# J-Link-OB-STM32F103C8T6.net
KiCad netlist of a schematic drawn in Altium Designer
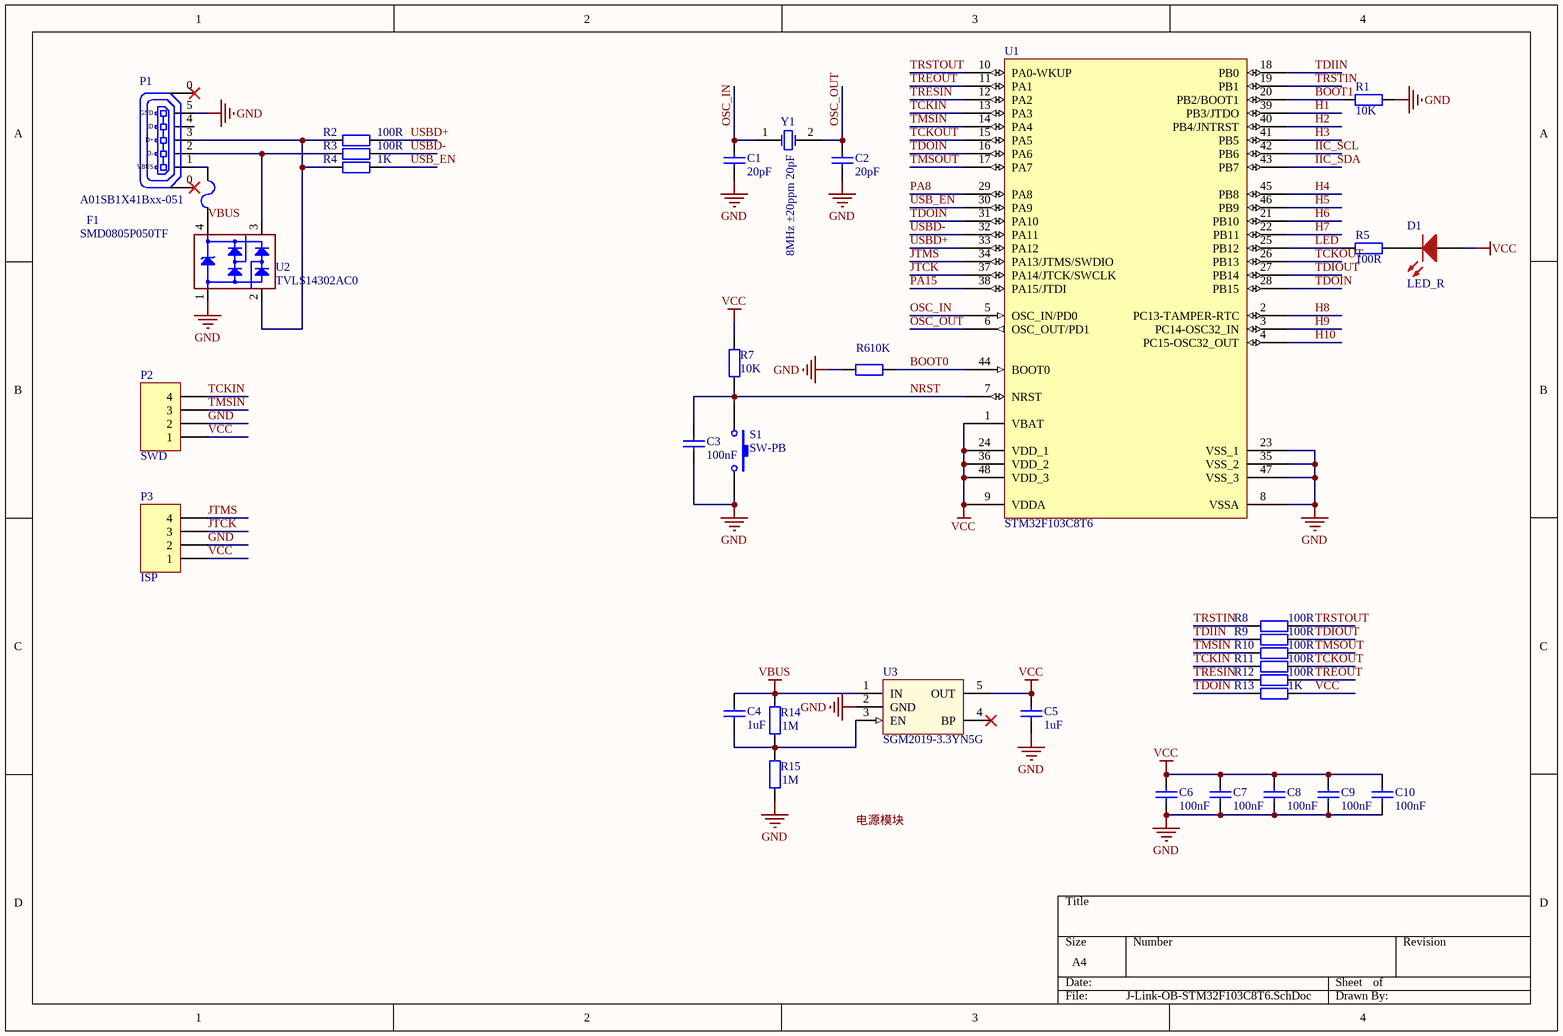
[diagram p0: J-Link-OB-STM32F103C8T6.SchDoc]

(export (version "E")
  (design (tool "Eeschema 10.0.6"))
  (components
    (comp (ref "C1")
      (value "20pF")
      (footprint "CAP0603")
      (description "0603, C0G, 20pF, ±5%, 50V, CL")
      (fields (field (name "PARTNUMBER") "CL10C200JB8NNNC") (field (name "MANUFACTURER") "Samsung"))
      (libsource (lib "Samsung") (part "Cap 20pF/±5%/50V/0603"))
    )
    (comp (ref "C2")
      (value "20pF")
      (footprint "CAP0603")
      (description "0603, C0G, 20pF, ±5%, 50V, CL")
      (fields (field (name "PARTNUMBER") "CL10C200JB8NNNC") (field (name "MANUFACTURER") "Samsung"))
      (libsource (lib "Samsung") (part "Cap 20pF/±5%/50V/0603"))
    )
    (comp (ref "C3")
      (value "100nF")
      (footprint "CAP0603")
      (description "0603, X7R, 100nF, ±10%, 50V, CL")
      (fields (field (name "PARTNUMBER") "CL10B104KB8NNNC") (field (name "MANUFACTURER") "Samsung"))
      (libsource (lib "Samsung") (part "Cap 100nF/±10%/50V/0603"))
    )
    (comp (ref "C4")
      (value "1uF")
      (footprint "CAP0603")
      (description "0603, X5R, 1uF, ±10%, 16V, CL")
      (fields (field (name "PARTNUMBER") "CL10A105KO8NNNC") (field (name "MANUFACTURER") "Samsung"))
      (libsource (lib "Samsung") (part "Cap 1uF/±10%/16V/0603"))
    )
    (comp (ref "C5")
      (value "1uF")
      (footprint "CAP0603")
      (description "0603, X5R, 1uF, ±10%, 16V, CL")
      (fields (field (name "PARTNUMBER") "CL10A105KO8NNNC") (field (name "MANUFACTURER") "Samsung"))
      (libsource (lib "Samsung") (part "Cap 1uF/±10%/16V/0603"))
    )
    (comp (ref "C6")
      (value "100nF")
      (footprint "CAP0603")
      (description "0603, X7R, 100nF, ±10%, 50V, CL")
      (fields (field (name "PARTNUMBER") "CL10B104KB8NNNC") (field (name "MANUFACTURER") "Samsung"))
      (libsource (lib "Samsung") (part "Cap 100nF/±10%/50V/0603"))
    )
    (comp (ref "C7")
      (value "100nF")
      (footprint "CAP0603")
      (description "0603, X7R, 100nF, ±10%, 50V, CL")
      (fields (field (name "PARTNUMBER") "CL10B104KB8NNNC") (field (name "MANUFACTURER") "Samsung"))
      (libsource (lib "Samsung") (part "Cap 100nF/±10%/50V/0603"))
    )
    (comp (ref "C8")
      (value "100nF")
      (footprint "CAP0603")
      (description "0603, X7R, 100nF, ±10%, 50V, CL")
      (fields (field (name "PARTNUMBER") "CL10B104KB8NNNC") (field (name "MANUFACTURER") "Samsung"))
      (libsource (lib "Samsung") (part "Cap 100nF/±10%/50V/0603"))
    )
    (comp (ref "C9")
      (value "100nF")
      (footprint "CAP0603")
      (description "0603, X7R, 100nF, ±10%, 50V, CL")
      (fields (field (name "PARTNUMBER") "CL10B104KB8NNNC") (field (name "MANUFACTURER") "Samsung"))
      (libsource (lib "Samsung") (part "Cap 100nF/±10%/50V/0603"))
    )
    (comp (ref "C10")
      (value "100nF")
      (footprint "CAP0603")
      (description "0603, X7R, 100nF, ±10%, 50V, CL")
      (fields (field (name "PARTNUMBER") "CL10B104KB8NNNC") (field (name "MANUFACTURER") "Samsung"))
      (libsource (lib "Samsung") (part "Cap 100nF/±10%/50V/0603"))
    )
    (comp (ref "D1")
      (value "LED_R")
      (footprint "19-21")
      (description "SMD0603 LED, 2-Pin 19-21, Pb-Free, Tape and Reel")
      (fields (field (name "MANUFACTURER") "Everlight") (field (name "PARTNUMBER") "19-21/R7C-AN2Q1B/3T"))
      (libsource (lib "Everlight") (part "LED_19-21/R7C-AN2Q1B/3T"))
    )
    (comp (ref "F1")
      (value "SMD0805P050TF")
      (footprint "SMD0805P050TF")
      (description "Over Current Protection, Resettable Fuses-PPTC, SMD0805 Series, I(hold) 0.05~1.25A")
      (fields (field (name "MANUFACTURER") "Shenzhen Ruilongyuan"))
      (libsource (lib "RuiLon") (part "SMD0805P050TF"))
    )
    (comp (ref "P1")
      (value "A01SB1X41Bxx-051")
      (footprint "A01SB1X41Bxx-051")
      (description "Micro USB, 7-Pin SMT-Micro-B, no Flange, Pitch 10.25mm")
      (fields (field (name "MANUFACTURER") "XinNanTian"))
      (libsource (lib "micro USB") (part "C40956/5P"))
    )
    (comp (ref "P2")
      (value "SWD")
      (footprint "HDR1X4H")
      (description "Header, 4-Pin, Right Angle")
      (fields (field (name "PUBLISHER") "Altium Limited"))
      (libsource (lib "Miscellaneous_Connectors") (part "Header 4H"))
    )
    (comp (ref "P3")
      (value "ISP")
      (footprint "HDR1X4")
      (description "Header, 4-Pin")
      (fields (field (name "PUBLISHER") "Altium Limited"))
      (libsource (lib "Miscellaneous Connectors") (part "Header 4"))
    )
    (comp (ref "R1")
      (value "10K")
      (footprint "RES0603")
      (description "10KΩ, ±1%, 0603, RC")
      (fields (field (name "PARTNUMBER") "RC0603FR-0710KL") (field (name "MANUFACTURER") "Yageo"))
      (libsource (lib "") (part "Res 10KΩ/±1%/0603_1"))
    )
    (comp (ref "R2")
      (value "100R")
      (footprint "RES0603")
      (description "100Ω, ±1%, 0603, RC")
      (fields (field (name "PARTNUMBER") "RC0603FR-07100RL") (field (name "MANUFACTURER") "Yageo"))
      (libsource (lib "YAGEO") (part "Res 100Ω/±1%/0603"))
    )
    (comp (ref "R3")
      (value "100R")
      (footprint "RES0603")
      (description "100Ω, ±1%, 0603, RC")
      (fields (field (name "PARTNUMBER") "RC0603FR-07100RL") (field (name "MANUFACTURER") "Yageo"))
      (libsource (lib "YAGEO") (part "Res 100Ω/±1%/0603"))
    )
    (comp (ref "R4")
      (value "1K")
      (footprint "RES0603")
      (description "100Ω, ±1%, 0603, RC")
      (fields (field (name "PARTNUMBER") "RC0603FR-07100RL") (field (name "MANUFACTURER") "Yageo"))
      (libsource (lib "YAGEO") (part "Res 100Ω/±1%/0603"))
    )
    (comp (ref "R5")
      (value "100R")
      (footprint "RES0603")
      (description "100Ω, ±5%, 0603, RC")
      (fields (field (name "PARTNUMBER") "RC0603JR-07100RL") (field (name "MANUFACTURER") "Yageo"))
      (libsource (lib "YAGEO") (part "Res 100Ω/±5%/0603"))
    )
    (comp (ref "R6")
      (value "10K")
      (footprint "RES0603")
      (description "10KΩ, ±1%, 0603, RC")
      (fields (field (name "PARTNUMBER") "RC0603FR-0710KL") (field (name "MANUFACTURER") "Yageo"))
      (libsource (lib "") (part "Res 10KΩ/±1%/0603_1"))
    )
    (comp (ref "R7")
      (value "10K")
      (footprint "RES0603")
      (description "10KΩ, ±1%, 0603, RC")
      (fields (field (name "PARTNUMBER") "RC0603FR-0710KL") (field (name "MANUFACTURER") "Yageo"))
      (libsource (lib "YAGEO") (part "Res 10KΩ/±1%/0603"))
    )
    (comp (ref "R8")
      (value "100R")
      (footprint "RES0603")
      (description "100Ω, ±1%, 0603, RC")
      (fields (field (name "PARTNUMBER") "RC0603FR-07100RL") (field (name "MANUFACTURER") "Yageo"))
      (libsource (lib "YAGEO") (part "Res 100Ω/±1%/0603"))
    )
    (comp (ref "R9")
      (value "100R")
      (footprint "RES0603")
      (description "100Ω, ±1%, 0603, RC")
      (fields (field (name "PARTNUMBER") "RC0603FR-07100RL") (field (name "MANUFACTURER") "Yageo"))
      (libsource (lib "YAGEO") (part "Res 100Ω/±1%/0603"))
    )
    (comp (ref "R10")
      (value "100R")
      (footprint "RES0603")
      (description "100Ω, ±1%, 0603, RC")
      (fields (field (name "PARTNUMBER") "RC0603FR-07100RL") (field (name "MANUFACTURER") "Yageo"))
      (libsource (lib "YAGEO") (part "Res 100Ω/±1%/0603"))
    )
    (comp (ref "R11")
      (value "100R")
      (footprint "RES0603")
      (description "100Ω, ±1%, 0603, RC")
      (fields (field (name "PARTNUMBER") "RC0603FR-07100RL") (field (name "MANUFACTURER") "Yageo"))
      (libsource (lib "YAGEO") (part "Res 100Ω/±1%/0603"))
    )
    (comp (ref "R12")
      (value "100R")
      (footprint "RES0603")
      (description "100Ω, ±1%, 0603, RC")
      (fields (field (name "PARTNUMBER") "RC0603FR-07100RL") (field (name "MANUFACTURER") "Yageo"))
      (libsource (lib "YAGEO") (part "Res 100Ω/±1%/0603"))
    )
    (comp (ref "R13")
      (value "1K")
      (footprint "RES0603")
      (description "100Ω, ±1%, 0603, RC")
      (fields (field (name "PARTNUMBER") "RC0603FR-07100RL") (field (name "MANUFACTURER") "Yageo"))
      (libsource (lib "YAGEO") (part "Res 100Ω/±1%/0603"))
    )
    (comp (ref "R14")
      (value "1M")
      (footprint "RES0603")
      (description "1MΩ, ±5%, 0603, RC")
      (fields (field (name "PARTNUMBER") "RC0603JR-071ML") (field (name "MANUFACTURER") "Yageo"))
      (libsource (lib "YAGEO") (part "Res 1MΩ/±5%/0603"))
    )
    (comp (ref "R15")
      (value "1M")
      (footprint "RES0603")
      (description "1MΩ, ±5%, 0603, RC")
      (fields (field (name "PARTNUMBER") "RC0603JR-071ML") (field (name "MANUFACTURER") "Yageo"))
      (libsource (lib "YAGEO") (part "Res 1MΩ/±5%/0603"))
    )
    (comp (ref "S1")
      (value "SW-PB")
      (footprint "SW-SKRK-SKRKAEE010")
      (description "Switch")
      (fields (field (name "PUBLISHER") "Altium Limited"))
      (libsource (lib "Miscellaneous Devices") (part "SW-PB"))
    )
    (comp (ref "U1")
      (value "STM32F103C8T6")
      (footprint "LQFP48_N")
      (description "STM32 ARM-based 32-bit MCU with 64 Kbytes Flash, 48-pin LQFP, Industrial Temperature")
      (fields (field (name "PUBLISHER") "Altium Limited"))
      (libsource (lib "ST_Microcontroller_32-Bit_STM32") (part "STM32F103C8T6"))
    )
    (comp (ref "U2")
      (value "TVLS14302AC0")
      (footprint "SOT-143-4L")
      (description "Multi-Line TVS Array, 4-Pin SOT-143-4L, Pb-Free, Tape and Reel")
      (fields (field (name "MANUFACTURER") "INPAQ"))
      (libsource (lib "INPAQ") (part "TVS_TVLS14302AC0"))
    )
    (comp (ref "U3")
      (value "SGM2019-3.3YN5G")
      (footprint "SOT23-5_L")
      (description "Single Output LDO, 300 mA, 3.3V Fixed Out, 2.5 to 5.5 V Input, 5-Pin SOT-23")
      (fields (field (name "MANUFACTURER") "SG Micro Corp") (field (name "PARTNUMBER") "SGM2019-3.3YN5G/TR"))
      (libsource (lib "SG_Micro") (part "SGM2019-3.3YN5G"))
    )
    (comp (ref "Y1")
      (value "8MHz ±20ppm 20pF")
      (footprint "SMD-5032_2P")
      (description "贴片晶振")
      (libsource (lib "TXC") (part "SMD-5032_2P 8MHz 20ppm 20pF"))
    )
  )
  (nets
    (net (code "1") (name "/BOOT0") (class "Default")
      (node (ref "R6") (pin "2") (pinfunction "2_2") (pintype "passive"))
      (node (ref "U1") (pin "44") (pinfunction "BOOT0_44") (pintype "input"))
    )
    (net (code "2") (name "/BOOT1") (class "Default")
      (node (ref "R1") (pin "1") (pinfunction "1_1") (pintype "passive"))
      (node (ref "U1") (pin "20") (pinfunction "PB2/BOOT1_20") (pintype "bidirectional"))
    )
    (net (code "3") (name "/H1") (class "Default")
      (node (ref "U1") (pin "39") (pinfunction "PB3/JTDO_39") (pintype "bidirectional"))
    )
    (net (code "4") (name "/H2") (class "Default")
      (node (ref "U1") (pin "40") (pinfunction "PB4/JNTRST_40") (pintype "bidirectional"))
    )
    (net (code "5") (name "/H3") (class "Default")
      (node (ref "U1") (pin "41") (pinfunction "PB5_41") (pintype "bidirectional"))
    )
    (net (code "6") (name "/H4") (class "Default")
      (node (ref "U1") (pin "45") (pinfunction "PB8_45") (pintype "bidirectional"))
    )
    (net (code "7") (name "/H5") (class "Default")
      (node (ref "U1") (pin "46") (pinfunction "PB9_46") (pintype "bidirectional"))
    )
    (net (code "8") (name "/H6") (class "Default")
      (node (ref "U1") (pin "21") (pinfunction "PB10_21") (pintype "bidirectional"))
    )
    (net (code "9") (name "/H7") (class "Default")
      (node (ref "U1") (pin "22") (pinfunction "PB11_22") (pintype "bidirectional"))
    )
    (net (code "10") (name "/H8") (class "Default")
      (node (ref "U1") (pin "2") (pinfunction "PC13-TAMPER-RTC_2") (pintype "bidirectional"))
    )
    (net (code "11") (name "/H9") (class "Default")
      (node (ref "U1") (pin "3") (pinfunction "PC14-OSC32_IN_3") (pintype "bidirectional"))
    )
    (net (code "12") (name "/H10") (class "Default")
      (node (ref "U1") (pin "4") (pinfunction "PC15-OSC32_OUT_4") (pintype "bidirectional"))
    )
    (net (code "13") (name "/IIC_SCL") (class "Default")
      (node (ref "U1") (pin "42") (pinfunction "PB6_42") (pintype "bidirectional"))
    )
    (net (code "14") (name "/IIC_SDA") (class "Default")
      (node (ref "U1") (pin "43") (pinfunction "PB7_43") (pintype "bidirectional"))
    )
    (net (code "15") (name "/JTCK") (class "Default")
      (node (ref "P3") (pin "3") (pinfunction "3_3") (pintype "passive"))
      (node (ref "U1") (pin "37") (pinfunction "PA14/JTCK/SWCLK_37") (pintype "bidirectional"))
    )
    (net (code "16") (name "/JTMS") (class "Default")
      (node (ref "P3") (pin "4") (pinfunction "4_4") (pintype "passive"))
      (node (ref "U1") (pin "34") (pinfunction "PA13/JTMS/SWDIO_34") (pintype "bidirectional"))
    )
    (net (code "17") (name "/LED") (class "Default")
      (node (ref "R5") (pin "1") (pinfunction "1_1") (pintype "passive"))
      (node (ref "U1") (pin "25") (pinfunction "PB12_25") (pintype "bidirectional"))
    )
    (net (code "18") (name "/NRST") (class "Default")
      (node (ref "C3") (pin "2") (pinfunction "2_2") (pintype "passive"))
      (node (ref "R7") (pin "1") (pinfunction "1_1") (pintype "passive"))
      (node (ref "S1") (pin "1") (pinfunction "1_1") (pintype "passive"))
      (node (ref "U1") (pin "7") (pinfunction "NRST_7") (pintype "bidirectional"))
    )
    (net (code "19") (name "/OSC_IN") (class "Default")
      (node (ref "C1") (pin "2") (pinfunction "2_2") (pintype "passive"))
      (node (ref "U1") (pin "5") (pinfunction "OSC_IN/PD0_5") (pintype "input"))
      (node (ref "Y1") (pin "1") (pinfunction "OSC1_1") (pintype "passive"))
    )
    (net (code "20") (name "/OSC_OUT") (class "Default")
      (node (ref "C2") (pin "2") (pinfunction "2_2") (pintype "passive"))
      (node (ref "U1") (pin "6") (pinfunction "OSC_OUT/PD1_6") (pintype "output"))
      (node (ref "Y1") (pin "2") (pinfunction "OSC2_2") (pintype "passive"))
    )
    (net (code "21") (name "/PA8") (class "Default")
      (node (ref "U1") (pin "29") (pinfunction "PA8_29") (pintype "bidirectional"))
    )
    (net (code "22") (name "/PA15") (class "Default")
      (node (ref "U1") (pin "38") (pinfunction "PA15/JTDI_38") (pintype "bidirectional"))
    )
    (net (code "23") (name "/TCKIN") (class "Default")
      (node (ref "P2") (pin "4") (pinfunction "4_4") (pintype "passive"))
      (node (ref "R11") (pin "2") (pinfunction "2_2") (pintype "passive"))
      (node (ref "U1") (pin "13") (pinfunction "PA3_13") (pintype "bidirectional"))
    )
    (net (code "24") (name "/TCKOUT") (class "Default")
      (node (ref "R11") (pin "1") (pinfunction "1_1") (pintype "passive"))
      (node (ref "U1") (pin "15") (pinfunction "PA5_15") (pintype "bidirectional"))
      (node (ref "U1") (pin "26") (pinfunction "PB13_26") (pintype "bidirectional"))
    )
    (net (code "25") (name "/TDIIN") (class "Default")
      (node (ref "R9") (pin "2") (pinfunction "2_2") (pintype "passive"))
      (node (ref "U1") (pin "18") (pinfunction "PB0_18") (pintype "bidirectional"))
    )
    (net (code "26") (name "/TDIOUT") (class "Default")
      (node (ref "R9") (pin "1") (pinfunction "1_1") (pintype "passive"))
      (node (ref "U1") (pin "27") (pinfunction "PB14_27") (pintype "bidirectional"))
    )
    (net (code "27") (name "/TDOIN") (class "Default")
      (node (ref "R13") (pin "2") (pinfunction "2_2") (pintype "passive"))
      (node (ref "U1") (pin "16") (pinfunction "PA6_16") (pintype "bidirectional"))
      (node (ref "U1") (pin "28") (pinfunction "PB15_28") (pintype "bidirectional"))
      (node (ref "U1") (pin "31") (pinfunction "PA10_31") (pintype "bidirectional"))
    )
    (net (code "28") (name "/TMSIN") (class "Default")
      (node (ref "P2") (pin "3") (pinfunction "3_3") (pintype "passive"))
      (node (ref "R10") (pin "2") (pinfunction "2_2") (pintype "passive"))
      (node (ref "U1") (pin "14") (pinfunction "PA4_14") (pintype "bidirectional"))
    )
    (net (code "29") (name "/TMSOUT") (class "Default")
      (node (ref "R10") (pin "1") (pinfunction "1_1") (pintype "passive"))
      (node (ref "U1") (pin "17") (pinfunction "PA7_17") (pintype "bidirectional"))
    )
    (net (code "30") (name "/TREOUT") (class "Default")
      (node (ref "R12") (pin "1") (pinfunction "1_1") (pintype "passive"))
      (node (ref "U1") (pin "11") (pinfunction "PA1_11") (pintype "bidirectional"))
    )
    (net (code "31") (name "/TRESIN") (class "Default")
      (node (ref "R12") (pin "2") (pinfunction "2_2") (pintype "passive"))
      (node (ref "U1") (pin "12") (pinfunction "PA2_12") (pintype "bidirectional"))
    )
    (net (code "32") (name "/TRSTIN") (class "Default")
      (node (ref "R8") (pin "2") (pinfunction "2_2") (pintype "passive"))
      (node (ref "U1") (pin "19") (pinfunction "PB1_19") (pintype "bidirectional"))
    )
    (net (code "33") (name "/TRSTOUT") (class "Default")
      (node (ref "R8") (pin "1") (pinfunction "1_1") (pintype "passive"))
      (node (ref "U1") (pin "10") (pinfunction "PA0-WKUP_10") (pintype "bidirectional"))
    )
    (net (code "34") (name "/USBD+") (class "Default")
      (node (ref "R2") (pin "1") (pinfunction "1_1") (pintype "passive"))
      (node (ref "U1") (pin "33") (pinfunction "PA12_33") (pintype "bidirectional"))
    )
    (net (code "35") (name "/USBD-") (class "Default")
      (node (ref "R3") (pin "1") (pinfunction "1_1") (pintype "passive"))
      (node (ref "U1") (pin "32") (pinfunction "PA11_32") (pintype "bidirectional"))
    )
    (net (code "36") (name "/USB_EN") (class "Default")
      (node (ref "R4") (pin "1") (pinfunction "1_1") (pintype "passive"))
      (node (ref "U1") (pin "30") (pinfunction "PA9_30") (pintype "bidirectional"))
    )
    (net (code "37") (name "GND") (class "Default")
      (node (ref "C1") (pin "1") (pinfunction "1_1") (pintype "passive"))
      (node (ref "C10") (pin "1") (pinfunction "1_1") (pintype "passive"))
      (node (ref "C2") (pin "1") (pinfunction "1_1") (pintype "passive"))
      (node (ref "C3") (pin "1") (pinfunction "1_1") (pintype "passive"))
      (node (ref "C5") (pin "1") (pinfunction "1_1") (pintype "passive"))
      (node (ref "C6") (pin "1") (pinfunction "1_1") (pintype "passive"))
      (node (ref "C7") (pin "1") (pinfunction "1_1") (pintype "passive"))
      (node (ref "C8") (pin "1") (pinfunction "1_1") (pintype "passive"))
      (node (ref "C9") (pin "1") (pinfunction "1_1") (pintype "passive"))
      (node (ref "P1") (pin "5") (pinfunction "GND_5") (pintype "power_in"))
      (node (ref "P2") (pin "2") (pinfunction "2_2") (pintype "passive"))
      (node (ref "P3") (pin "2") (pinfunction "2_2") (pintype "passive"))
      (node (ref "R1") (pin "2") (pinfunction "2_2") (pintype "passive"))
      (node (ref "R15") (pin "1") (pinfunction "1_1") (pintype "passive"))
      (node (ref "R6") (pin "1") (pinfunction "1_1") (pintype "passive"))
      (node (ref "S1") (pin "2") (pinfunction "2_2") (pintype "passive"))
      (node (ref "U1") (pin "23") (pinfunction "VSS_1_23") (pintype "power_in"))
      (node (ref "U1") (pin "35") (pinfunction "VSS_2_35") (pintype "power_in"))
      (node (ref "U1") (pin "47") (pinfunction "VSS_3_47") (pintype "power_in"))
      (node (ref "U1") (pin "8") (pinfunction "VSSA_8") (pintype "power_in"))
      (node (ref "U2") (pin "1") (pinfunction "GND_1") (pintype "power_in"))
      (node (ref "U3") (pin "2") (pinfunction "GND_2") (pintype "power_in"))
    )
    (net (code "38") (name "Net-(D1-K)") (class "Default")
      (node (ref "D1") (pin "2") (pinfunction "K_2") (pintype "passive"))
      (node (ref "R5") (pin "2") (pinfunction "2_2") (pintype "passive"))
    )
    (net (code "39") (name "Net-(P1-D+)") (class "Default")
      (node (ref "P1") (pin "3") (pinfunction "D+_3") (pintype "passive"))
      (node (ref "R2") (pin "2") (pinfunction "2_2") (pintype "passive"))
      (node (ref "R4") (pin "2") (pinfunction "2_2") (pintype "passive"))
      (node (ref "U2") (pin "2") (pinfunction "I/O1_2") (pintype "power_in"))
    )
    (net (code "40") (name "Net-(P1-D-)") (class "Default")
      (node (ref "P1") (pin "2") (pinfunction "D-_2") (pintype "passive"))
      (node (ref "R3") (pin "2") (pinfunction "2_2") (pintype "passive"))
      (node (ref "U2") (pin "3") (pinfunction "I/O2_3") (pintype "power_in"))
    )
    (net (code "41") (name "Net-(P1-VBUS)") (class "Default")
      (node (ref "F1") (pin "2") (pinfunction "2_2") (pintype "passive"))
      (node (ref "P1") (pin "1") (pinfunction "VBUS_1") (pintype "power_in"))
    )
    (net (code "42") (name "Net-(U3-EN)") (class "Default")
      (node (ref "C4") (pin "1") (pinfunction "1_1") (pintype "passive"))
      (node (ref "R14") (pin "1") (pinfunction "1_1") (pintype "passive"))
      (node (ref "R15") (pin "2") (pinfunction "2_2") (pintype "passive"))
      (node (ref "U3") (pin "3") (pinfunction "EN_3") (pintype "input"))
    )
    (net (code "43") (name "VBUS") (class "Default")
      (node (ref "C4") (pin "2") (pinfunction "2_2") (pintype "passive"))
      (node (ref "F1") (pin "1") (pinfunction "1_1") (pintype "passive"))
      (node (ref "R14") (pin "2") (pinfunction "2_2") (pintype "passive"))
      (node (ref "U2") (pin "4") (pinfunction "VDD_4") (pintype "power_in"))
      (node (ref "U3") (pin "1") (pinfunction "IN_1") (pintype "power_in"))
    )
    (net (code "44") (name "VCC") (class "Default")
      (node (ref "C10") (pin "2") (pinfunction "2_2") (pintype "passive"))
      (node (ref "C5") (pin "2") (pinfunction "2_2") (pintype "passive"))
      (node (ref "C6") (pin "2") (pinfunction "2_2") (pintype "passive"))
      (node (ref "C7") (pin "2") (pinfunction "2_2") (pintype "passive"))
      (node (ref "C8") (pin "2") (pinfunction "2_2") (pintype "passive"))
      (node (ref "C9") (pin "2") (pinfunction "2_2") (pintype "passive"))
      (node (ref "D1") (pin "1") (pinfunction "A_1") (pintype "passive"))
      (node (ref "P2") (pin "1") (pinfunction "1_1") (pintype "passive"))
      (node (ref "P3") (pin "1") (pinfunction "1_1") (pintype "passive"))
      (node (ref "R13") (pin "1") (pinfunction "1_1") (pintype "passive"))
      (node (ref "R7") (pin "2") (pinfunction "2_2") (pintype "passive"))
      (node (ref "U1") (pin "1") (pinfunction "VBAT_1") (pintype "power_in"))
      (node (ref "U1") (pin "24") (pinfunction "VDD_1_24") (pintype "power_in"))
      (node (ref "U1") (pin "36") (pinfunction "VDD_2_36") (pintype "power_in"))
      (node (ref "U1") (pin "48") (pinfunction "VDD_3_48") (pintype "power_in"))
      (node (ref "U1") (pin "9") (pinfunction "VDDA_9") (pintype "power_in"))
      (node (ref "U3") (pin "5") (pinfunction "OUT_5") (pintype "power_in"))
    )
    (net (code "45") (name "unconnected-(P1-ID-Pad4)") (class "Default")
      (node (ref "P1") (pin "4") (pinfunction "ID_4") (pintype "passive"))
    )
    (net (code "46") (name "unconnected-(P1-PAD-Pad0)") (class "Default")
      (node (ref "P1") (pin "0") (pinfunction "PAD_0") (pintype "power_in+no_connect"))
    )
    (net (code "47") (name "unconnected-(P1-PAD-Pad0)_1") (class "Default")
      (node (ref "P1") (pin "0") (pinfunction "PAD_0") (pintype "power_in+no_connect"))
    )
    (net (code "48") (name "unconnected-(U3-BP-Pad4)") (class "Default")
      (node (ref "U3") (pin "4") (pinfunction "BP_4") (pintype "passive+no_connect"))
    )
  )
)
